# 180_schematic_3_layer.net
KiCad netlist of a schematic drawn in EAGLE
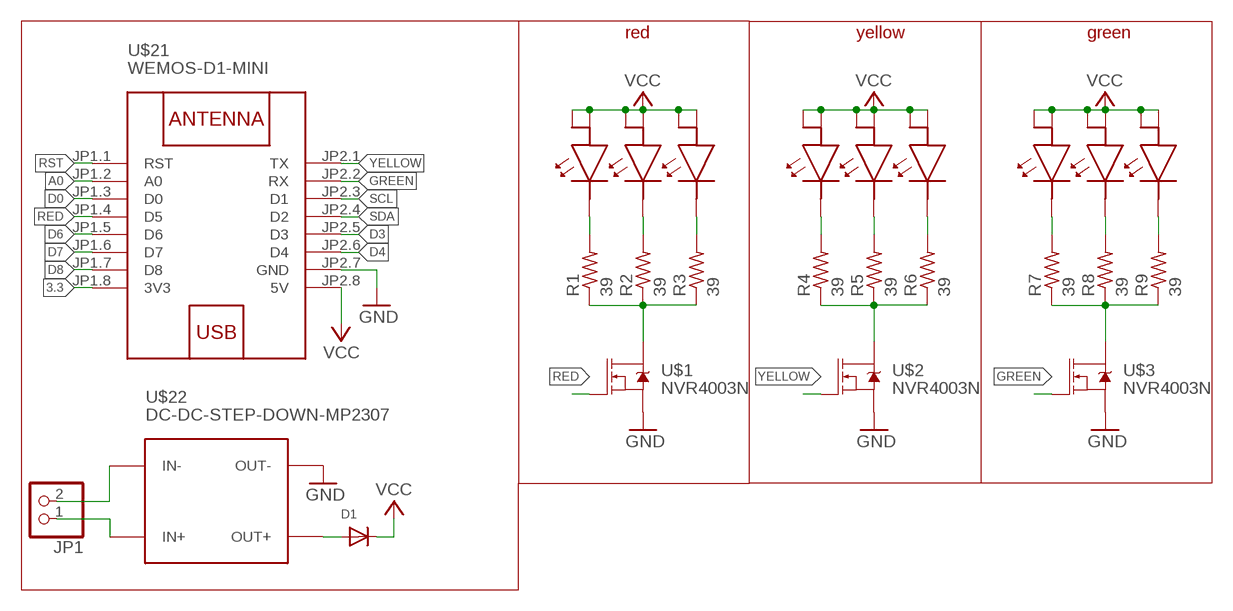
[diagram p0: schematic, sheet 1]

(export (version "E")
  (design (tool "Eeschema 10.0.6"))
  (components
    (comp (ref "D1")
      (value "DIODESOD-123")
      (footprint "eagle-import:SOD-123")
      (libsource (lib "eagle-import") (part "DIODESOD-123"))
    )
    (comp (ref "JP1")
      (value "PINHD-1X2")
      (footprint "eagle-import:1X02")
      (libsource (lib "eagle-import") (part "PINHD-1X2"))
    )
    (comp (ref "R1")
      (value "39")
      (footprint "eagle-import:R1206W")
      (libsource (lib "eagle-import") (part "R-US_R1206W"))
    )
    (comp (ref "R2")
      (value "39")
      (footprint "eagle-import:R1206W")
      (libsource (lib "eagle-import") (part "R-US_R1206W"))
    )
    (comp (ref "R3")
      (value "39")
      (footprint "eagle-import:R1206W")
      (libsource (lib "eagle-import") (part "R-US_R1206W"))
    )
    (comp (ref "R4")
      (value "39")
      (footprint "eagle-import:R1206W")
      (libsource (lib "eagle-import") (part "R-US_R1206W"))
    )
    (comp (ref "R5")
      (value "39")
      (footprint "eagle-import:R1206W")
      (libsource (lib "eagle-import") (part "R-US_R1206W"))
    )
    (comp (ref "R6")
      (value "39")
      (footprint "eagle-import:R1206W")
      (libsource (lib "eagle-import") (part "R-US_R1206W"))
    )
    (comp (ref "R7")
      (value "39")
      (footprint "eagle-import:R1206W")
      (libsource (lib "eagle-import") (part "R-US_R1206W"))
    )
    (comp (ref "R8")
      (value "39")
      (footprint "eagle-import:R1206W")
      (libsource (lib "eagle-import") (part "R-US_R1206W"))
    )
    (comp (ref "R9")
      (value "39")
      (footprint "eagle-import:R1206W")
      (libsource (lib "eagle-import") (part "R-US_R1206W"))
    )
    (comp (ref "U$1")
      (value "NVR4003N")
      (footprint "eagle-import:SOT23")
      (libsource (lib "eagle-import") (part "NVR4003N"))
    )
    (comp (ref "U$2")
      (value "NVR4003N")
      (footprint "eagle-import:SOT23")
      (libsource (lib "eagle-import") (part "NVR4003N"))
    )
    (comp (ref "U$3")
      (value "NVR4003N")
      (footprint "eagle-import:SOT23")
      (libsource (lib "eagle-import") (part "NVR4003N"))
    )
    (comp (ref "U$6")
      (value "5730LED")
      (footprint "eagle-import:5730LED")
      (libsource (lib "eagle-import") (part "5730LED"))
    )
    (comp (ref "U$7")
      (value "5730LED")
      (footprint "eagle-import:5730LED")
      (libsource (lib "eagle-import") (part "5730LED"))
    )
    (comp (ref "U$8")
      (value "5730LED")
      (footprint "eagle-import:5730LED")
      (libsource (lib "eagle-import") (part "5730LED"))
    )
    (comp (ref "U$9")
      (value "5730LED")
      (footprint "eagle-import:5730LED")
      (libsource (lib "eagle-import") (part "5730LED"))
    )
    (comp (ref "U$10")
      (value "5730LED")
      (footprint "eagle-import:5730LED")
      (libsource (lib "eagle-import") (part "5730LED"))
    )
    (comp (ref "U$11")
      (value "5730LED")
      (footprint "eagle-import:5730LED")
      (libsource (lib "eagle-import") (part "5730LED"))
    )
    (comp (ref "U$12")
      (value "5730LED")
      (footprint "eagle-import:5730LED")
      (libsource (lib "eagle-import") (part "5730LED"))
    )
    (comp (ref "U$13")
      (value "5730LED")
      (footprint "eagle-import:5730LED")
      (libsource (lib "eagle-import") (part "5730LED"))
    )
    (comp (ref "U$14")
      (value "5730LED")
      (footprint "eagle-import:5730LED")
      (libsource (lib "eagle-import") (part "5730LED"))
    )
    (comp (ref "U$21")
      (value "WEMOS-D1-MINI")
      (footprint "eagle-import:WEMOS-D1-MINI")
      (libsource (lib "eagle-import") (part "WEMOS-D1-MINI"))
    )
    (comp (ref "U$22")
      (value "DC-DC-STEP-DOWN-MP2307")
      (footprint "eagle-import:DC-DC-STEP-DOWN-MP2307")
      (libsource (lib "eagle-import") (part "DC-DC-STEP-DOWN-MP2307"))
    )
  )
  (nets
    (net (code "1") (name "3.3") (class "Default")
      (node (ref "U$21") (pin "JP1.8") (pinfunction "3V3_JP1.8") (pintype "power_in"))
    )
    (net (code "2") (name "A0") (class "Default")
      (node (ref "U$21") (pin "JP1.2") (pinfunction "A0_JP1.2") (pintype "bidirectional"))
    )
    (net (code "3") (name "D0") (class "Default")
      (node (ref "U$21") (pin "JP1.3") (pinfunction "D0_JP1.3") (pintype "bidirectional"))
    )
    (net (code "4") (name "D3") (class "Default")
      (node (ref "U$21") (pin "JP2.5") (pinfunction "D3_JP2.5") (pintype "bidirectional"))
    )
    (net (code "5") (name "D4") (class "Default")
      (node (ref "U$21") (pin "JP2.6") (pinfunction "D4_JP2.6") (pintype "bidirectional"))
    )
    (net (code "6") (name "D6") (class "Default")
      (node (ref "U$21") (pin "JP1.5") (pinfunction "D6_JP1.5") (pintype "bidirectional"))
    )
    (net (code "7") (name "D7") (class "Default")
      (node (ref "U$21") (pin "JP1.6") (pinfunction "D7_JP1.6") (pintype "bidirectional"))
    )
    (net (code "8") (name "D8") (class "Default")
      (node (ref "U$21") (pin "JP1.7") (pinfunction "D8_JP1.7") (pintype "bidirectional"))
    )
    (net (code "9") (name "GND") (class "Default")
      (node (ref "U$1") (pin "3") (pinfunction "S_3") (pintype "bidirectional"))
      (node (ref "U$2") (pin "3") (pinfunction "S_3") (pintype "bidirectional"))
      (node (ref "U$21") (pin "JP2.7") (pinfunction "GND_JP2.7") (pintype "power_in"))
      (node (ref "U$22") (pin "OUT-") (pinfunction "OUT-_OUT-") (pintype "bidirectional"))
      (node (ref "U$3") (pin "3") (pinfunction "S_3") (pintype "bidirectional"))
    )
    (net (code "10") (name "GREEN") (class "Default")
      (node (ref "U$21") (pin "JP2.2") (pinfunction "RX_JP2.2") (pintype "bidirectional"))
      (node (ref "U$3") (pin "2") (pinfunction "G_2") (pintype "bidirectional"))
    )
    (net (code "11") (name "Net-(D1-PadA)") (class "Default")
      (node (ref "D1") (pin "A") (pinfunction "A_A") (pintype "passive"))
      (node (ref "U$22") (pin "OUT+") (pinfunction "OUT+_OUT+") (pintype "bidirectional"))
    )
    (net (code "12") (name "Net-(JP1-Pad1)") (class "Default")
      (node (ref "JP1") (pin "1") (pinfunction "1_1") (pintype "passive"))
      (node (ref "U$22") (pin "IN+") (pinfunction "IN+_IN+") (pintype "bidirectional"))
    )
    (net (code "13") (name "Net-(JP1-Pad2)") (class "Default")
      (node (ref "JP1") (pin "2") (pinfunction "2_2") (pintype "passive"))
      (node (ref "U$22") (pin "IN-") (pinfunction "IN-_IN-") (pintype "bidirectional"))
    )
    (net (code "14") (name "Net-(R1-Pad2)") (class "Default")
      (node (ref "R1") (pin "2") (pinfunction "2_2") (pintype "passive"))
      (node (ref "U$6") (pin "P$2") (pinfunction "P$2_P$2") (pintype "bidirectional"))
    )
    (net (code "15") (name "Net-(R2-Pad2)") (class "Default")
      (node (ref "R2") (pin "2") (pinfunction "2_2") (pintype "passive"))
      (node (ref "U$7") (pin "P$2") (pinfunction "P$2_P$2") (pintype "bidirectional"))
    )
    (net (code "16") (name "Net-(R3-Pad2)") (class "Default")
      (node (ref "R3") (pin "2") (pinfunction "2_2") (pintype "passive"))
      (node (ref "U$8") (pin "P$2") (pinfunction "P$2_P$2") (pintype "bidirectional"))
    )
    (net (code "17") (name "Net-(R4-Pad2)") (class "Default")
      (node (ref "R4") (pin "2") (pinfunction "2_2") (pintype "passive"))
      (node (ref "U$9") (pin "P$2") (pinfunction "P$2_P$2") (pintype "bidirectional"))
    )
    (net (code "18") (name "Net-(R5-Pad2)") (class "Default")
      (node (ref "R5") (pin "2") (pinfunction "2_2") (pintype "passive"))
      (node (ref "U$10") (pin "P$2") (pinfunction "P$2_P$2") (pintype "bidirectional"))
    )
    (net (code "19") (name "Net-(R6-Pad2)") (class "Default")
      (node (ref "R6") (pin "2") (pinfunction "2_2") (pintype "passive"))
      (node (ref "U$11") (pin "P$2") (pinfunction "P$2_P$2") (pintype "bidirectional"))
    )
    (net (code "20") (name "Net-(R7-Pad2)") (class "Default")
      (node (ref "R7") (pin "2") (pinfunction "2_2") (pintype "passive"))
      (node (ref "U$12") (pin "P$2") (pinfunction "P$2_P$2") (pintype "bidirectional"))
    )
    (net (code "21") (name "Net-(R8-Pad2)") (class "Default")
      (node (ref "R8") (pin "2") (pinfunction "2_2") (pintype "passive"))
      (node (ref "U$13") (pin "P$2") (pinfunction "P$2_P$2") (pintype "bidirectional"))
    )
    (net (code "22") (name "Net-(R9-Pad2)") (class "Default")
      (node (ref "R9") (pin "2") (pinfunction "2_2") (pintype "passive"))
      (node (ref "U$14") (pin "P$2") (pinfunction "P$2_P$2") (pintype "bidirectional"))
    )
    (net (code "23") (name "Net-(U$1-D)") (class "Default")
      (node (ref "R1") (pin "1") (pinfunction "1_1") (pintype "passive"))
      (node (ref "R2") (pin "1") (pinfunction "1_1") (pintype "passive"))
      (node (ref "R3") (pin "1") (pinfunction "1_1") (pintype "passive"))
      (node (ref "U$1") (pin "1") (pinfunction "D_1") (pintype "bidirectional"))
    )
    (net (code "24") (name "Net-(U$2-D)") (class "Default")
      (node (ref "R4") (pin "1") (pinfunction "1_1") (pintype "passive"))
      (node (ref "R5") (pin "1") (pinfunction "1_1") (pintype "passive"))
      (node (ref "R6") (pin "1") (pinfunction "1_1") (pintype "passive"))
      (node (ref "U$2") (pin "1") (pinfunction "D_1") (pintype "bidirectional"))
    )
    (net (code "25") (name "Net-(U$3-D)") (class "Default")
      (node (ref "R7") (pin "1") (pinfunction "1_1") (pintype "passive"))
      (node (ref "R8") (pin "1") (pinfunction "1_1") (pintype "passive"))
      (node (ref "R9") (pin "1") (pinfunction "1_1") (pintype "passive"))
      (node (ref "U$3") (pin "1") (pinfunction "D_1") (pintype "bidirectional"))
    )
    (net (code "26") (name "RED") (class "Default")
      (node (ref "U$1") (pin "2") (pinfunction "G_2") (pintype "bidirectional"))
      (node (ref "U$21") (pin "JP1.4") (pinfunction "D5_JP1.4") (pintype "bidirectional"))
    )
    (net (code "27") (name "RST") (class "Default")
      (node (ref "U$21") (pin "JP1.1") (pinfunction "RST_JP1.1") (pintype "bidirectional"))
    )
    (net (code "28") (name "SCL") (class "Default")
      (node (ref "U$21") (pin "JP2.3") (pinfunction "D1_JP2.3") (pintype "bidirectional"))
    )
    (net (code "29") (name "SDA") (class "Default")
      (node (ref "U$21") (pin "JP2.4") (pinfunction "D2_JP2.4") (pintype "bidirectional"))
    )
    (net (code "30") (name "VCC") (class "Default")
      (node (ref "D1") (pin "C") (pinfunction "C_C") (pintype "passive"))
      (node (ref "U$10") (pin "P$1") (pinfunction "P$1_P$1") (pintype "bidirectional"))
      (node (ref "U$10") (pin "P$3") (pinfunction "P$3_P$3") (pintype "bidirectional"))
      (node (ref "U$11") (pin "P$1") (pinfunction "P$1_P$1") (pintype "bidirectional"))
      (node (ref "U$11") (pin "P$3") (pinfunction "P$3_P$3") (pintype "bidirectional"))
      (node (ref "U$12") (pin "P$1") (pinfunction "P$1_P$1") (pintype "bidirectional"))
      (node (ref "U$12") (pin "P$3") (pinfunction "P$3_P$3") (pintype "bidirectional"))
      (node (ref "U$13") (pin "P$1") (pinfunction "P$1_P$1") (pintype "bidirectional"))
      (node (ref "U$13") (pin "P$3") (pinfunction "P$3_P$3") (pintype "bidirectional"))
      (node (ref "U$14") (pin "P$1") (pinfunction "P$1_P$1") (pintype "bidirectional"))
      (node (ref "U$14") (pin "P$3") (pinfunction "P$3_P$3") (pintype "bidirectional"))
      (node (ref "U$21") (pin "JP2.8") (pinfunction "5V_JP2.8") (pintype "power_in"))
      (node (ref "U$6") (pin "P$1") (pinfunction "P$1_P$1") (pintype "bidirectional"))
      (node (ref "U$6") (pin "P$3") (pinfunction "P$3_P$3") (pintype "bidirectional"))
      (node (ref "U$7") (pin "P$1") (pinfunction "P$1_P$1") (pintype "bidirectional"))
      (node (ref "U$7") (pin "P$3") (pinfunction "P$3_P$3") (pintype "bidirectional"))
      (node (ref "U$8") (pin "P$1") (pinfunction "P$1_P$1") (pintype "bidirectional"))
      (node (ref "U$8") (pin "P$3") (pinfunction "P$3_P$3") (pintype "bidirectional"))
      (node (ref "U$9") (pin "P$1") (pinfunction "P$1_P$1") (pintype "bidirectional"))
      (node (ref "U$9") (pin "P$3") (pinfunction "P$3_P$3") (pintype "bidirectional"))
    )
    (net (code "31") (name "YELLOW") (class "Default")
      (node (ref "U$2") (pin "2") (pinfunction "G_2") (pintype "bidirectional"))
      (node (ref "U$21") (pin "JP2.1") (pinfunction "TX_JP2.1") (pintype "bidirectional"))
    )
  )
)
